# watch.net
KiCad netlist of a schematic drawn in EAGLE
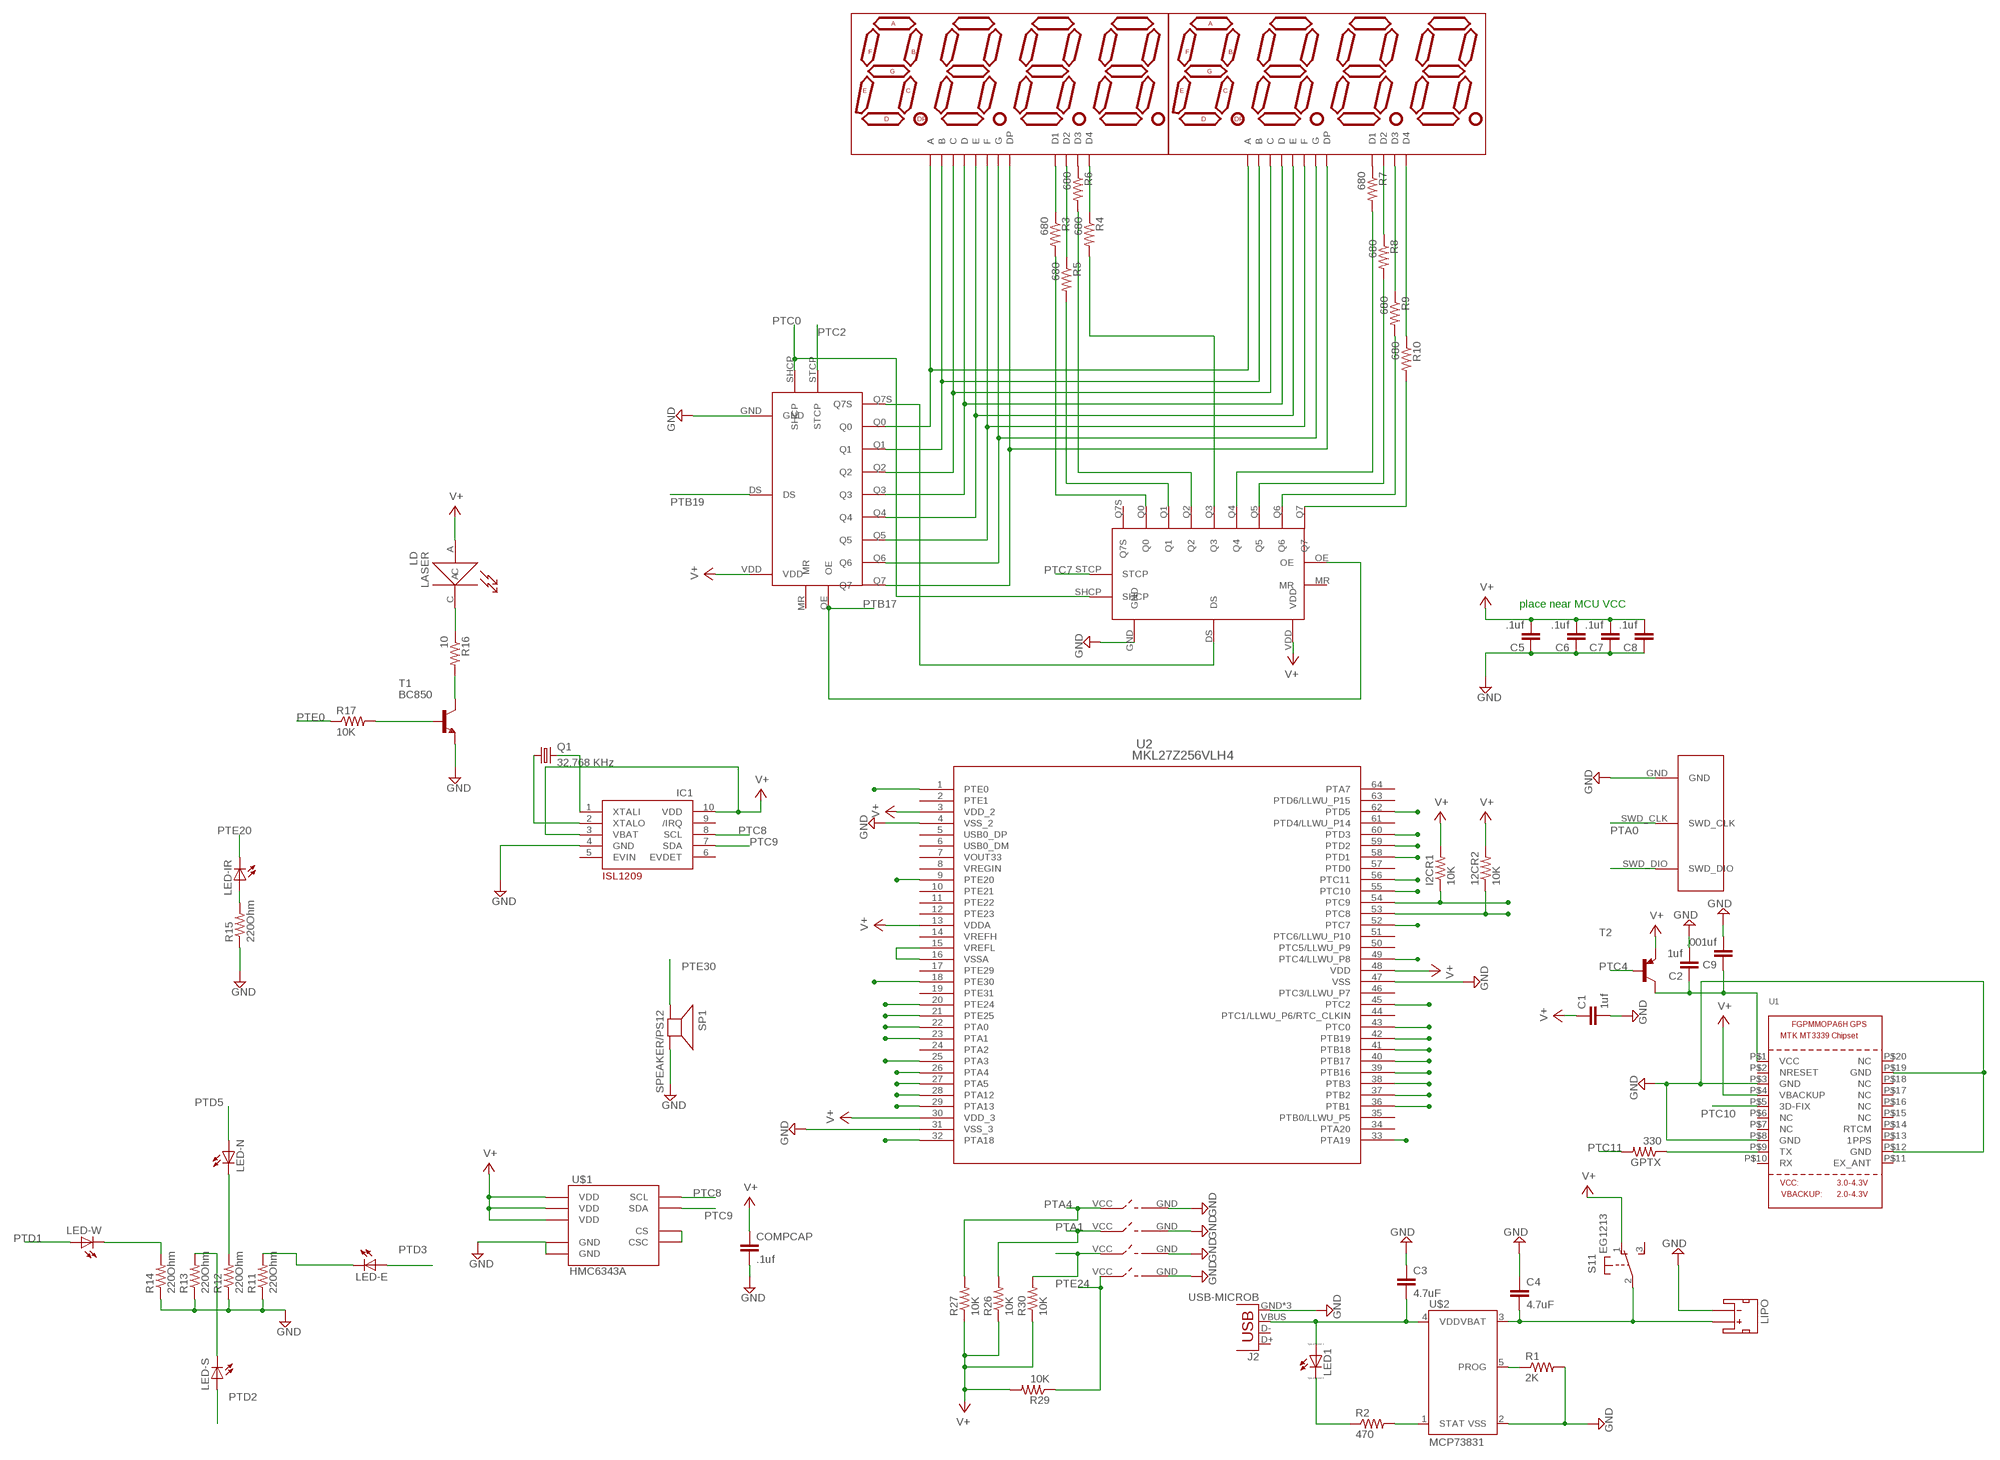
[diagram p0: schematic, sheet 1]

(export (version "E")
  (design (tool "Eeschema 10.0.6"))
  (components
    (comp (ref "12CR2")
      (value "10K")
      (footprint "eagle-import:0603-RES")
      (libsource (lib "eagle-import") (part "RESISTOR0603"))
    )
    (comp (ref "C1")
      (value "1uf")
      (footprint "eagle-import:0603")
      (libsource (lib "eagle-import") (part "CAP0603"))
    )
    (comp (ref "C2")
      (value "1uf")
      (footprint "eagle-import:0603")
      (libsource (lib "eagle-import") (part "CAP0603"))
    )
    (comp (ref "C3")
      (value "4.7uF")
      (footprint "eagle-import:0603-CAP")
      (libsource (lib "eagle-import") (part "0.1UF-25V(+80/-20%)(0603)"))
    )
    (comp (ref "C4")
      (value "4.7uF")
      (footprint "eagle-import:0603-CAP")
      (libsource (lib "eagle-import") (part "0.1UF-25V(+80/-20%)(0603)"))
    )
    (comp (ref "C5")
      (value ".1uf")
      (footprint "eagle-import:0603")
      (libsource (lib "eagle-import") (part "CAP0603"))
    )
    (comp (ref "C6")
      (value ".1uf")
      (footprint "eagle-import:0603")
      (libsource (lib "eagle-import") (part "CAP0603"))
    )
    (comp (ref "C7")
      (value ".1uf")
      (footprint "eagle-import:0603")
      (libsource (lib "eagle-import") (part "CAP0603"))
    )
    (comp (ref "C8")
      (value ".1uf")
      (footprint "eagle-import:0603")
      (libsource (lib "eagle-import") (part "CAP0603"))
    )
    (comp (ref "C9")
      (value ".001uf")
      (footprint "eagle-import:0603")
      (libsource (lib "eagle-import") (part "CAP0603"))
    )
    (comp (ref "COMPCAP")
      (value ".1uf")
      (footprint "eagle-import:0603")
      (libsource (lib "eagle-import") (part "CAP0603"))
    )
    (comp (ref "DISP1")
      (value "7-SEGMENT-4DIGIT-COUNTER-HP-BUBBLE")
      (footprint "eagle-import:DIL12")
      (libsource (lib "eagle-import") (part "7-SEGMENT-4DIGIT-COUNTER-HP-BUBBLE"))
    )
    (comp (ref "DISP2")
      (value "7-SEGMENT-4DIGIT-COUNTER-HP-BUBBLE")
      (footprint "eagle-import:DIL12")
      (libsource (lib "eagle-import") (part "7-SEGMENT-4DIGIT-COUNTER-HP-BUBBLE"))
    )
    (comp (ref "GPTX")
      (value "330")
      (footprint "eagle-import:0603-RES")
      (libsource (lib "eagle-import") (part "RESISTOR0603"))
    )
    (comp (ref "I2CR1")
      (value "10K")
      (footprint "eagle-import:0603-RES")
      (libsource (lib "eagle-import") (part "RESISTOR0603"))
    )
    (comp (ref "IC1")
      (value "ISL1209")
      (footprint "eagle-import:MSOP10")
      (libsource (lib "eagle-import") (part "ISL1209"))
    )
    (comp (ref "J2")
      (value "USB-MICROB")
      (footprint "eagle-import:USB-MICROB")
      (libsource (lib "eagle-import") (part "USB-MICROB"))
    )
    (comp (ref "LASER")
      (value "LD")
      (footprint "eagle-import:LD-FLUSH-WITH-JUMPER")
      (libsource (lib "eagle-import") (part "LD"))
    )
    (comp (ref "LED-E")
      (value "LED5MM")
      (footprint "eagle-import:LED5MM")
      (libsource (lib "eagle-import") (part "LED5MM"))
    )
    (comp (ref "LED-IR")
      (value "LED5MM")
      (footprint "eagle-import:LED5MM")
      (libsource (lib "eagle-import") (part "LED5MM"))
    )
    (comp (ref "LED-N")
      (value "LED5MM")
      (footprint "eagle-import:LED5MM")
      (libsource (lib "eagle-import") (part "LED5MM"))
    )
    (comp (ref "LED-S")
      (value "LED5MM")
      (footprint "eagle-import:LED5MM")
      (libsource (lib "eagle-import") (part "LED5MM"))
    )
    (comp (ref "LED-W")
      (value "LED5MM")
      (footprint "eagle-import:LED5MM")
      (libsource (lib "eagle-import") (part "LED5MM"))
    )
    (comp (ref "LED1")
      (value "LED_ESML0603")
      (footprint "eagle-import:LED_SML0603")
      (libsource (lib "eagle-import") (part "LED_ESML0603"))
    )
    (comp (ref "LIPO")
      (value "JST_2MM_MALE")
      (footprint "eagle-import:JST-2-SMD")
      (libsource (lib "eagle-import") (part "JST_2MM_MALE"))
    )
    (comp (ref "Q1")
      (value "32.768 KHz")
      (footprint "eagle-import:TC26H")
      (libsource (lib "eagle-import") (part "CRYSTALTC26H"))
    )
    (comp (ref "R1")
      (value "2K")
      (footprint "eagle-import:0603-RES")
      (libsource (lib "eagle-import") (part "RESISTOR0603"))
    )
    (comp (ref "R2")
      (value "470")
      (footprint "eagle-import:0603-RES")
      (libsource (lib "eagle-import") (part "RESISTOR0603"))
    )
    (comp (ref "R3")
      (value "680")
      (footprint "eagle-import:0603-RES")
      (libsource (lib "eagle-import") (part "RESISTOR0603"))
    )
    (comp (ref "R4")
      (value "680")
      (footprint "eagle-import:0603-RES")
      (libsource (lib "eagle-import") (part "RESISTOR0603"))
    )
    (comp (ref "R5")
      (value "680")
      (footprint "eagle-import:0603-RES")
      (libsource (lib "eagle-import") (part "RESISTOR0603"))
    )
    (comp (ref "R6")
      (value "680")
      (footprint "eagle-import:0603-RES")
      (libsource (lib "eagle-import") (part "RESISTOR0603"))
    )
    (comp (ref "R7")
      (value "680")
      (footprint "eagle-import:0603-RES")
      (libsource (lib "eagle-import") (part "RESISTOR0603"))
    )
    (comp (ref "R8")
      (value "680")
      (footprint "eagle-import:0603-RES")
      (libsource (lib "eagle-import") (part "RESISTOR0603"))
    )
    (comp (ref "R9")
      (value "680")
      (footprint "eagle-import:0603-RES")
      (libsource (lib "eagle-import") (part "RESISTOR0603"))
    )
    (comp (ref "R10")
      (value "680")
      (footprint "eagle-import:0603-RES")
      (libsource (lib "eagle-import") (part "RESISTOR0603"))
    )
    (comp (ref "R11")
      (value "220Ohm")
      (footprint "eagle-import:0603-RES")
      (libsource (lib "eagle-import") (part "RESISTOR0603"))
    )
    (comp (ref "R12")
      (value "220Ohm")
      (footprint "eagle-import:0603-RES")
      (libsource (lib "eagle-import") (part "RESISTOR0603"))
    )
    (comp (ref "R13")
      (value "220Ohm")
      (footprint "eagle-import:0603-RES")
      (libsource (lib "eagle-import") (part "RESISTOR0603"))
    )
    (comp (ref "R14")
      (value "220Ohm")
      (footprint "eagle-import:0603-RES")
      (libsource (lib "eagle-import") (part "RESISTOR0603"))
    )
    (comp (ref "R15")
      (value "220Ohm")
      (footprint "eagle-import:0603-RES")
      (libsource (lib "eagle-import") (part "RESISTOR0603"))
    )
    (comp (ref "R16")
      (value "10")
      (footprint "eagle-import:0603-RES")
      (libsource (lib "eagle-import") (part "RESISTOR0603"))
    )
    (comp (ref "R17")
      (value "10K")
      (footprint "eagle-import:0603-RES")
      (libsource (lib "eagle-import") (part "RESISTOR0603"))
    )
    (comp (ref "R26")
      (value "10K")
      (footprint "eagle-import:0603-RES")
      (libsource (lib "eagle-import") (part "RESISTOR0603"))
    )
    (comp (ref "R27")
      (value "10K")
      (footprint "eagle-import:0603-RES")
      (libsource (lib "eagle-import") (part "RESISTOR0603"))
    )
    (comp (ref "R29")
      (value "10K")
      (footprint "eagle-import:0603-RES")
      (libsource (lib "eagle-import") (part "RESISTOR0603"))
    )
    (comp (ref "R30")
      (value "10K")
      (footprint "eagle-import:0603-RES")
      (libsource (lib "eagle-import") (part "RESISTOR0603"))
    )
    (comp (ref "S1")
      (value "EG1213")
      (footprint "eagle-import:EG1213")
      (libsource (lib "eagle-import") (part "EG1213"))
    )
    (comp (ref "SP1")
      (value "SPEAKER/PS12")
      (footprint "eagle-import:PS12")
      (libsource (lib "eagle-import") (part "SPEAKER/PS12"))
    )
    (comp (ref "SWD_BREAKOUT")
      (value "SWD_BREAKOUTS")
      (footprint "eagle-import:SWD")
      (libsource (lib "eagle-import") (part "SWD_BREAKOUTS"))
    )
    (comp (ref "T1")
      (value "BC850")
      (footprint "eagle-import:SOT23")
      (libsource (lib "eagle-import") (part "BC850"))
    )
    (comp (ref "T2")
      (value "-PNP-SOT23-EBC")
      (footprint "eagle-import:SOT23-EBC")
      (libsource (lib "eagle-import") (part "-PNP-SOT23-EBC"))
    )
    (comp (ref "U$1")
      (value "HMC6343A")
      (footprint "eagle-import:LCC36")
      (libsource (lib "eagle-import") (part "HMC6343A"))
    )
    (comp (ref "U$2")
      (value "MCP73831")
      (footprint "eagle-import:SOT23-5")
      (libsource (lib "eagle-import") (part "MCP73831"))
    )
    (comp (ref "U$3")
      (value "DIPS")
      (footprint "eagle-import:DIPS")
      (libsource (lib "eagle-import") (part "DIPS"))
    )
    (comp (ref "U$4")
      (value "74HC595PW")
      (footprint "eagle-import:74HC595PW")
      (libsource (lib "eagle-import") (part "74HC595PW"))
    )
    (comp (ref "U$5")
      (value "74HC595PW")
      (footprint "eagle-import:74HC595PW")
      (libsource (lib "eagle-import") (part "74HC595PW"))
    )
    (comp (ref "U$7")
      (value "DIPS")
      (footprint "eagle-import:DIPS")
      (libsource (lib "eagle-import") (part "DIPS"))
    )
    (comp (ref "U$8")
      (value "DIPS")
      (footprint "eagle-import:DIPS")
      (libsource (lib "eagle-import") (part "DIPS"))
    )
    (comp (ref "U$9")
      (value "DIPS")
      (footprint "eagle-import:DIPS")
      (libsource (lib "eagle-import") (part "DIPS"))
    )
    (comp (ref "U1")
      (value "GPS_FGPMMOPA6H")
      (footprint "eagle-import:FGPMMOPA6H")
      (libsource (lib "eagle-import") (part "GPS_FGPMMOPA6H"))
    )
    (comp (ref "U2")
      (value "MKL27Z256VLH4")
      (footprint "eagle-import:LQFP-64_10X10X1.6")
      (fields (field (name "MANUFACTURER_PART_NUMBER") "mkl27z256vlh4"))
      (libsource (lib "eagle-import") (part "MKL27Z256VLH4"))
    )
  )
  (nets
    (net (code "1") (name "/PTA0") (class "Default")
      (node (ref "SWD_BREAKOUT") (pin "SWD_CLK") (pinfunction "SWD_CLK_SWD_CLK") (pintype "bidirectional"))
      (node (ref "U2") (pin "22") (pinfunction "PTA0_22") (pintype "bidirectional"))
    )
    (net (code "2") (name "/PTA1") (class "Default")
      (node (ref "R26") (pin "2") (pinfunction "2_2") (pintype "passive"))
      (node (ref "U$7") (pin "VCC") (pinfunction "V_VCC") (pintype "bidirectional"))
      (node (ref "U2") (pin "23") (pinfunction "PTA1_23") (pintype "bidirectional"))
    )
    (net (code "3") (name "/PTA3") (class "Default")
      (node (ref "SWD_BREAKOUT") (pin "SWD_DIO") (pinfunction "SWD_DIO_SWD_DIO") (pintype "bidirectional"))
      (node (ref "U2") (pin "25") (pinfunction "PTA3_25") (pintype "bidirectional"))
    )
    (net (code "4") (name "/PTA4") (class "Default")
      (node (ref "R27") (pin "2") (pinfunction "2_2") (pintype "passive"))
      (node (ref "U$3") (pin "VCC") (pinfunction "V_VCC") (pintype "bidirectional"))
      (node (ref "U2") (pin "26") (pinfunction "PTA4_26") (pintype "bidirectional"))
    )
    (net (code "5") (name "/PTB17") (class "Default")
      (node (ref "U$4") (pin "OE") (pinfunction "OE_OE") (pintype "bidirectional"))
      (node (ref "U$5") (pin "OE") (pinfunction "OE_OE") (pintype "bidirectional"))
      (node (ref "U2") (pin "40") (pinfunction "PTB17_40") (pintype "bidirectional"))
    )
    (net (code "6") (name "/PTB19") (class "Default")
      (node (ref "U$4") (pin "DS") (pinfunction "DS_DS") (pintype "bidirectional"))
      (node (ref "U2") (pin "42") (pinfunction "PTB19_42") (pintype "bidirectional"))
    )
    (net (code "7") (name "/PTC0") (class "Default")
      (node (ref "U$4") (pin "SHCP") (pinfunction "SHCP_SHCP") (pintype "bidirectional"))
      (node (ref "U$5") (pin "SHCP") (pinfunction "SHCP_SHCP") (pintype "bidirectional"))
      (node (ref "U2") (pin "43") (pinfunction "PTC0_43") (pintype "bidirectional"))
    )
    (net (code "8") (name "/PTC2") (class "Default")
      (node (ref "U$4") (pin "STCP") (pinfunction "STCP_STCP") (pintype "bidirectional"))
      (node (ref "U2") (pin "45") (pinfunction "PTC2_45") (pintype "bidirectional"))
    )
    (net (code "9") (name "/PTC4") (class "Default")
      (node (ref "T2") (pin "B") (pinfunction "B_B") (pintype "passive"))
      (node (ref "U2") (pin "49") (pinfunction "PTC4/LLWU_P8_49") (pintype "bidirectional"))
    )
    (net (code "10") (name "/PTC7") (class "Default")
      (node (ref "U$5") (pin "STCP") (pinfunction "STCP_STCP") (pintype "bidirectional"))
      (node (ref "U2") (pin "52") (pinfunction "PTC7_52") (pintype "bidirectional"))
    )
    (net (code "11") (name "/PTC8") (class "Default")
      (node (ref "12CR2") (pin "1") (pinfunction "1_1") (pintype "passive"))
      (node (ref "IC1") (pin "8") (pinfunction "SCL_8") (pintype "input"))
      (node (ref "U$1") (pin "32") (pinfunction "SCL_32") (pintype "bidirectional"))
      (node (ref "U2") (pin "53") (pinfunction "PTC8_53") (pintype "bidirectional"))
    )
    (net (code "12") (name "/PTC9") (class "Default")
      (node (ref "I2CR1") (pin "1") (pinfunction "1_1") (pintype "passive"))
      (node (ref "IC1") (pin "7") (pinfunction "SDA_7") (pintype "bidirectional"))
      (node (ref "U$1") (pin "36") (pinfunction "SDA_36") (pintype "bidirectional"))
      (node (ref "U2") (pin "54") (pinfunction "PTC9_54") (pintype "bidirectional"))
    )
    (net (code "13") (name "/PTC10") (class "Default")
      (node (ref "U1") (pin "P$5") (pinfunction "3D-FIX_P$5") (pintype "bidirectional"))
      (node (ref "U2") (pin "55") (pinfunction "PTC10_55") (pintype "bidirectional"))
    )
    (net (code "14") (name "/PTC11") (class "Default")
      (node (ref "GPTX") (pin "2") (pinfunction "2_2") (pintype "passive"))
      (node (ref "U2") (pin "56") (pinfunction "PTC11_56") (pintype "bidirectional"))
    )
    (net (code "15") (name "/PTD1") (class "Default")
      (node (ref "LED-W") (pin "A") (pinfunction "A_A") (pintype "passive"))
      (node (ref "U2") (pin "58") (pinfunction "PTD1_58") (pintype "bidirectional"))
    )
    (net (code "16") (name "/PTD2") (class "Default")
      (node (ref "LED-S") (pin "A") (pinfunction "A_A") (pintype "passive"))
      (node (ref "U2") (pin "59") (pinfunction "PTD2_59") (pintype "bidirectional"))
    )
    (net (code "17") (name "/PTD3") (class "Default")
      (node (ref "LED-E") (pin "A") (pinfunction "A_A") (pintype "passive"))
      (node (ref "U2") (pin "60") (pinfunction "PTD3_60") (pintype "bidirectional"))
    )
    (net (code "18") (name "/PTD5") (class "Default")
      (node (ref "LED-N") (pin "A") (pinfunction "A_A") (pintype "passive"))
      (node (ref "U2") (pin "62") (pinfunction "PTD5_62") (pintype "bidirectional"))
    )
    (net (code "19") (name "/PTE0") (class "Default")
      (node (ref "R17") (pin "1") (pinfunction "1_1") (pintype "passive"))
      (node (ref "U2") (pin "1") (pinfunction "PTE0_1") (pintype "bidirectional"))
    )
    (net (code "20") (name "/PTE20") (class "Default")
      (node (ref "LED-IR") (pin "K") (pinfunction "C_K") (pintype "passive"))
      (node (ref "U2") (pin "9") (pinfunction "PTE20_9") (pintype "bidirectional"))
    )
    (net (code "21") (name "/PTE24") (class "Default")
      (node (ref "R29") (pin "1") (pinfunction "1_1") (pintype "passive"))
      (node (ref "U$9") (pin "VCC") (pinfunction "V_VCC") (pintype "bidirectional"))
      (node (ref "U2") (pin "20") (pinfunction "PTE24_20") (pintype "bidirectional"))
    )
    (net (code "22") (name "/PTE25") (class "Default")
      (node (ref "R30") (pin "2") (pinfunction "2_2") (pintype "passive"))
      (node (ref "U$8") (pin "VCC") (pinfunction "V_VCC") (pintype "bidirectional"))
      (node (ref "U2") (pin "21") (pinfunction "PTE25_21") (pintype "bidirectional"))
    )
    (net (code "23") (name "/PTE30") (class "Default")
      (node (ref "SP1") (pin "P$1") (pinfunction "+_P$1") (pintype "passive"))
      (node (ref "U2") (pin "18") (pinfunction "PTE30_18") (pintype "bidirectional"))
    )
    (net (code "24") (name "/VREFH") (class "Default")
      (node (ref "U2") (pin "14") (pinfunction "VREFH_14") (pintype "power_in"))
    )
    (net (code "25") (name "GND") (class "Default")
      (node (ref "C1") (pin "2") (pinfunction "2_2") (pintype "passive"))
      (node (ref "C2") (pin "2") (pinfunction "2_2") (pintype "passive"))
      (node (ref "C3") (pin "1") (pinfunction "1_1") (pintype "passive"))
      (node (ref "C4") (pin "1") (pinfunction "1_1") (pintype "passive"))
      (node (ref "C5") (pin "1") (pinfunction "1_1") (pintype "passive"))
      (node (ref "C6") (pin "1") (pinfunction "1_1") (pintype "passive"))
      (node (ref "C7") (pin "1") (pinfunction "1_1") (pintype "passive"))
      (node (ref "C8") (pin "1") (pinfunction "1_1") (pintype "passive"))
      (node (ref "C9") (pin "2") (pinfunction "2_2") (pintype "passive"))
      (node (ref "COMPCAP") (pin "2") (pinfunction "2_2") (pintype "passive"))
      (node (ref "IC1") (pin "4") (pinfunction "GND_4") (pintype "power_in"))
      (node (ref "J2") (pin "GND") (pinfunction "GND_GND") (pintype "bidirectional"))
      (node (ref "J2") (pin "MT1") (pinfunction "GND_MT1") (pintype "bidirectional"))
      (node (ref "J2") (pin "MT2") (pinfunction "GND_MT2") (pintype "bidirectional"))
      (node (ref "LIPO") (pin "1") (pinfunction "-_1") (pintype "bidirectional"))
      (node (ref "R1") (pin "2") (pinfunction "2_2") (pintype "passive"))
      (node (ref "R11") (pin "1") (pinfunction "1_1") (pintype "passive"))
      (node (ref "R12") (pin "1") (pinfunction "1_1") (pintype "passive"))
      (node (ref "R13") (pin "1") (pinfunction "1_1") (pintype "passive"))
      (node (ref "R14") (pin "1") (pinfunction "1_1") (pintype "passive"))
      (node (ref "R15") (pin "1") (pinfunction "1_1") (pintype "passive"))
      (node (ref "SP1") (pin "P$2") (pinfunction "-_P$2") (pintype "passive"))
      (node (ref "SWD_BREAKOUT") (pin "GND") (pinfunction "GND_GND") (pintype "bidirectional"))
      (node (ref "T1") (pin "2") (pinfunction "E_2") (pintype "passive"))
      (node (ref "U$1") (pin "25") (pinfunction "GND_25") (pintype "bidirectional"))
      (node (ref "U$1") (pin "29") (pinfunction "GND_29") (pintype "bidirectional"))
      (node (ref "U$2") (pin "2") (pinfunction "VSS_2") (pintype "power_in"))
      (node (ref "U$3") (pin "GND") (pinfunction "GND_GND") (pintype "bidirectional"))
      (node (ref "U$4") (pin "GND") (pinfunction "GND_GND") (pintype "bidirectional"))
      (node (ref "U$5") (pin "GND") (pinfunction "GND_GND") (pintype "bidirectional"))
      (node (ref "U$7") (pin "GND") (pinfunction "GND_GND") (pintype "bidirectional"))
      (node (ref "U$8") (pin "GND") (pinfunction "GND_GND") (pintype "bidirectional"))
      (node (ref "U$9") (pin "GND") (pinfunction "GND_GND") (pintype "bidirectional"))
      (node (ref "U1") (pin "P$12") (pinfunction "GND_P$12") (pintype "bidirectional"))
      (node (ref "U1") (pin "P$19") (pinfunction "GND_P$19") (pintype "bidirectional"))
      (node (ref "U1") (pin "P$3") (pinfunction "GND_P$3") (pintype "bidirectional"))
      (node (ref "U1") (pin "P$8") (pinfunction "GND_P$8") (pintype "bidirectional"))
      (node (ref "U2") (pin "31") (pinfunction "VSS_3_31") (pintype "power_in"))
      (node (ref "U2") (pin "4") (pinfunction "VSS_2_4") (pintype "power_in"))
      (node (ref "U2") (pin "47") (pinfunction "VSS_47") (pintype "power_in"))
    )
    (net (code "26") (name "Net-(DISP1-A)") (class "Default")
      (node (ref "DISP1") (pin "12") (pinfunction "A_12") (pintype "bidirectional"))
      (node (ref "DISP2") (pin "12") (pinfunction "A_12") (pintype "bidirectional"))
      (node (ref "U$4") (pin "Q0") (pinfunction "Q0_Q0") (pintype "bidirectional"))
    )
    (net (code "27") (name "Net-(DISP1-B)") (class "Default")
      (node (ref "DISP1") (pin "11") (pinfunction "B_11") (pintype "bidirectional"))
      (node (ref "DISP2") (pin "11") (pinfunction "B_11") (pintype "bidirectional"))
      (node (ref "U$4") (pin "Q1") (pinfunction "Q1_Q1") (pintype "bidirectional"))
    )
    (net (code "28") (name "Net-(DISP1-C)") (class "Default")
      (node (ref "DISP1") (pin "3") (pinfunction "C_3") (pintype "bidirectional"))
      (node (ref "DISP2") (pin "3") (pinfunction "C_3") (pintype "bidirectional"))
      (node (ref "U$4") (pin "Q2") (pinfunction "Q2_Q2") (pintype "bidirectional"))
    )
    (net (code "29") (name "Net-(DISP1-D)") (class "Default")
      (node (ref "DISP1") (pin "8") (pinfunction "D_8") (pintype "bidirectional"))
      (node (ref "DISP2") (pin "8") (pinfunction "D_8") (pintype "bidirectional"))
      (node (ref "U$4") (pin "Q3") (pinfunction "Q3_Q3") (pintype "bidirectional"))
    )
    (net (code "30") (name "Net-(DISP1-D1)") (class "Default")
      (node (ref "DISP1") (pin "1") (pinfunction "D1_1") (pintype "bidirectional"))
      (node (ref "R3") (pin "1") (pinfunction "1_1") (pintype "passive"))
    )
    (net (code "31") (name "Net-(DISP1-D2)") (class "Default")
      (node (ref "DISP1") (pin "10") (pinfunction "D2_10") (pintype "bidirectional"))
      (node (ref "R5") (pin "1") (pinfunction "1_1") (pintype "passive"))
    )
    (net (code "32") (name "Net-(DISP1-D3)") (class "Default")
      (node (ref "DISP1") (pin "4") (pinfunction "D3_4") (pintype "bidirectional"))
      (node (ref "R6") (pin "1") (pinfunction "1_1") (pintype "passive"))
    )
    (net (code "33") (name "Net-(DISP1-D4)") (class "Default")
      (node (ref "DISP1") (pin "6") (pinfunction "D4_6") (pintype "bidirectional"))
      (node (ref "R4") (pin "1") (pinfunction "1_1") (pintype "passive"))
    )
    (net (code "34") (name "Net-(DISP1-DP)") (class "Default")
      (node (ref "DISP1") (pin "5") (pinfunction "DP_5") (pintype "bidirectional"))
      (node (ref "DISP2") (pin "5") (pinfunction "DP_5") (pintype "bidirectional"))
      (node (ref "U$4") (pin "Q7") (pinfunction "Q7_Q7") (pintype "bidirectional"))
    )
    (net (code "35") (name "Net-(DISP1-E)") (class "Default")
      (node (ref "DISP1") (pin "2") (pinfunction "E_2") (pintype "bidirectional"))
      (node (ref "DISP2") (pin "2") (pinfunction "E_2") (pintype "bidirectional"))
      (node (ref "U$4") (pin "Q4") (pinfunction "Q4_Q4") (pintype "bidirectional"))
    )
    (net (code "36") (name "Net-(DISP1-F)") (class "Default")
      (node (ref "DISP1") (pin "9") (pinfunction "F_9") (pintype "bidirectional"))
      (node (ref "DISP2") (pin "9") (pinfunction "F_9") (pintype "bidirectional"))
      (node (ref "U$4") (pin "Q5") (pinfunction "Q5_Q5") (pintype "bidirectional"))
    )
    (net (code "37") (name "Net-(DISP1-G)") (class "Default")
      (node (ref "DISP1") (pin "7") (pinfunction "G_7") (pintype "bidirectional"))
      (node (ref "DISP2") (pin "7") (pinfunction "G_7") (pintype "bidirectional"))
      (node (ref "U$4") (pin "Q6") (pinfunction "Q6_Q6") (pintype "bidirectional"))
    )
    (net (code "38") (name "Net-(DISP2-D1)") (class "Default")
      (node (ref "DISP2") (pin "1") (pinfunction "D1_1") (pintype "bidirectional"))
      (node (ref "R7") (pin "1") (pinfunction "1_1") (pintype "passive"))
    )
    (net (code "39") (name "Net-(DISP2-D2)") (class "Default")
      (node (ref "DISP2") (pin "10") (pinfunction "D2_10") (pintype "bidirectional"))
      (node (ref "R8") (pin "1") (pinfunction "1_1") (pintype "passive"))
    )
    (net (code "40") (name "Net-(DISP2-D3)") (class "Default")
      (node (ref "DISP2") (pin "4") (pinfunction "D3_4") (pintype "bidirectional"))
      (node (ref "R9") (pin "1") (pinfunction "1_1") (pintype "passive"))
    )
    (net (code "41") (name "Net-(DISP2-D4)") (class "Default")
      (node (ref "DISP2") (pin "6") (pinfunction "D4_6") (pintype "bidirectional"))
      (node (ref "R10") (pin "1") (pinfunction "1_1") (pintype "passive"))
    )
    (net (code "42") (name "Net-(IC1-XTALI)") (class "Default")
      (node (ref "IC1") (pin "1") (pinfunction "XTALI_1") (pintype "input"))
      (node (ref "Q1") (pin "2") (pinfunction "2_2") (pintype "passive"))
    )
    (net (code "43") (name "Net-(IC1-XTALO)") (class "Default")
      (node (ref "IC1") (pin "2") (pinfunction "XTALO_2") (pintype "output"))
      (node (ref "Q1") (pin "1") (pinfunction "1_1") (pintype "passive"))
    )
    (net (code "44") (name "Net-(LASER-PadC)") (class "Default")
      (node (ref "LASER") (pin "C") (pinfunction "C_C") (pintype "passive"))
      (node (ref "R16") (pin "1") (pinfunction "1_1") (pintype "passive"))
    )
    (net (code "45") (name "Net-(LED-E-C)") (class "Default")
      (node (ref "LED-E") (pin "K") (pinfunction "C_K") (pintype "passive"))
      (node (ref "R11") (pin "2") (pinfunction "2_2") (pintype "passive"))
    )
    (net (code "46") (name "Net-(LED-IR-PadA)") (class "Default")
      (node (ref "LED-IR") (pin "A") (pinfunction "A_A") (pintype "passive"))
      (node (ref "R15") (pin "2") (pinfunction "2_2") (pintype "passive"))
    )
    (net (code "47") (name "Net-(LED-N-C)") (class "Default")
      (node (ref "LED-N") (pin "K") (pinfunction "C_K") (pintype "passive"))
      (node (ref "R12") (pin "2") (pinfunction "2_2") (pintype "passive"))
    )
    (net (code "48") (name "Net-(LED-S-C)") (class "Default")
      (node (ref "LED-S") (pin "K") (pinfunction "C_K") (pintype "passive"))
      (node (ref "R13") (pin "2") (pinfunction "2_2") (pintype "passive"))
    )
    (net (code "49") (name "Net-(LED-W-C)") (class "Default")
      (node (ref "LED-W") (pin "K") (pinfunction "C_K") (pintype "passive"))
      (node (ref "R14") (pin "2") (pinfunction "2_2") (pintype "passive"))
    )
    (net (code "50") (name "Net-(LED1-PadC)") (class "Default")
      (node (ref "LED1") (pin "C") (pinfunction "C_C") (pintype "passive"))
      (node (ref "R2") (pin "1") (pinfunction "1_1") (pintype "passive"))
    )
    (net (code "51") (name "Net-(LIPO-+)") (class "Default")
      (node (ref "C4") (pin "2") (pinfunction "2_2") (pintype "passive"))
      (node (ref "LIPO") (pin "2") (pinfunction "+_2") (pintype "bidirectional"))
      (node (ref "S1") (pin "2") (pinfunction "P_2") (pintype "passive"))
      (node (ref "U$2") (pin "3") (pinfunction "VBAT_3") (pintype "power_in"))
    )
    (net (code "52") (name "Net-(R3-Pad2)") (class "Default")
      (node (ref "R3") (pin "2") (pinfunction "2_2") (pintype "passive"))
      (node (ref "U$5") (pin "Q0") (pinfunction "Q0_Q0") (pintype "bidirectional"))
    )
    (net (code "53") (name "Net-(R4-Pad2)") (class "Default")
      (node (ref "R4") (pin "2") (pinfunction "2_2") (pintype "passive"))
      (node (ref "U$5") (pin "Q3") (pinfunction "Q3_Q3") (pintype "bidirectional"))
    )
    (net (code "54") (name "Net-(R5-Pad2)") (class "Default")
      (node (ref "R5") (pin "2") (pinfunction "2_2") (pintype "passive"))
      (node (ref "U$5") (pin "Q1") (pinfunction "Q1_Q1") (pintype "bidirectional"))
    )
    (net (code "55") (name "Net-(R6-Pad2)") (class "Default")
      (node (ref "R6") (pin "2") (pinfunction "2_2") (pintype "passive"))
      (node (ref "U$5") (pin "Q2") (pinfunction "Q2_Q2") (pintype "bidirectional"))
    )
    (net (code "56") (name "Net-(R7-Pad2)") (class "Default")
      (node (ref "R7") (pin "2") (pinfunction "2_2") (pintype "passive"))
      (node (ref "U$5") (pin "Q4") (pinfunction "Q4_Q4") (pintype "bidirectional"))
    )
    (net (code "57") (name "Net-(R8-Pad2)") (class "Default")
      (node (ref "R8") (pin "2") (pinfunction "2_2") (pintype "passive"))
      (node (ref "U$5") (pin "Q5") (pinfunction "Q5_Q5") (pintype "bidirectional"))
    )
    (net (code "58") (name "Net-(R9-Pad2)") (class "Default")
      (node (ref "R9") (pin "2") (pinfunction "2_2") (pintype "passive"))
      (node (ref "U$5") (pin "Q6") (pinfunction "Q6_Q6") (pintype "bidirectional"))
    )
    (net (code "59") (name "Net-(R10-Pad2)") (class "Default")
      (node (ref "R10") (pin "2") (pinfunction "2_2") (pintype "passive"))
      (node (ref "U$5") (pin "Q7") (pinfunction "Q7_Q7") (pintype "bidirectional"))
    )
    (net (code "60") (name "Net-(T1-B)") (class "Default")
      (node (ref "R17") (pin "2") (pinfunction "2_2") (pintype "passive"))
      (node (ref "T1") (pin "1") (pinfunction "B_1") (pintype "passive"))
    )
    (net (code "61") (name "Net-(T1-C)") (class "Default")
      (node (ref "R16") (pin "2") (pinfunction "2_2") (pintype "passive"))
      (node (ref "T1") (pin "3") (pinfunction "C_3") (pintype "passive"))
    )
    (net (code "62") (name "Net-(U$1-CS)") (class "Default")
      (node (ref "U$1") (pin "22") (pinfunction "CS_22") (pintype "bidirectional"))
      (node (ref "U$1") (pin "35") (pinfunction "CSC_35") (pintype "bidirectional"))
    )
    (net (code "63") (name "Net-(U$2-PROG)") (class "Default")
      (node (ref "R1") (pin "1") (pinfunction "1_1") (pintype "passive"))
      (node (ref "U$2") (pin "5") (pinfunction "PROG_5") (pintype "input"))
    )
    (net (code "64") (name "Net-(U$2-STAT)") (class "Default")
      (node (ref "R2") (pin "2") (pinfunction "2_2") (pintype "passive"))
      (node (ref "U$2") (pin "1") (pinfunction "STAT_1") (pintype "output"))
    )
    (net (code "65") (name "Net-(U$2-VDD)") (class "Default")
      (node (ref "C3") (pin "2") (pinfunction "2_2") (pintype "passive"))
      (node (ref "J2") (pin "VBUS") (pinfunction "VBUS_VBUS") (pintype "bidirectional"))
      (node (ref "LED1") (pin "A") (pinfunction "A_A") (pintype "passive"))
      (node (ref "U$2") (pin "4") (pinfunction "VDD_4") (pintype "power_in"))
    )
    (net (code "66") (name "Net-(U$4-PadQ7S)") (class "Default")
      (node (ref "U$4") (pin "Q7S") (pinfunction "Q7S_Q7S") (pintype "bidirectional"))
      (node (ref "U$5") (pin "DS") (pinfunction "DS_DS") (pintype "bidirectional"))
    )
    (net (code "67") (name "Net-(U1-TX)") (class "Default")
      (node (ref "GPTX") (pin "1") (pinfunction "1_1") (pintype "passive"))
      (node (ref "U1") (pin "P$9") (pinfunction "TX_P$9") (pintype "bidirectional"))
    )
    (net (code "68") (name "Net-(U1-VCC)") (class "Default")
      (node (ref "C2") (pin "1") (pinfunction "1_1") (pintype "passive"))
      (node (ref "C9") (pin "1") (pinfunction "1_1") (pintype "passive"))
      (node (ref "T2") (pin "C") (pinfunction "C_C") (pintype "passive"))
      (node (ref "U1") (pin "P$1") (pinfunction "VCC_P$1") (pintype "bidirectional"))
    )
    (net (code "69") (name "Net-(U2-VREFL)") (class "Default")
      (node (ref "U2") (pin "15") (pinfunction "VREFL_15") (pintype "power_in"))
      (node (ref "U2") (pin "16") (pinfunction "VSSA_16") (pintype "power_in"))
    )
    (net (code "70") (name "V+") (class "Default")
      (node (ref "12CR2") (pin "2") (pinfunction "2_2") (pintype "passive"))
      (node (ref "C1") (pin "1") (pinfunction "1_1") (pintype "passive"))
      (node (ref "C5") (pin "2") (pinfunction "2_2") (pintype "passive"))
      (node (ref "C6") (pin "2") (pinfunction "2_2") (pintype "passive"))
      (node (ref "C7") (pin "2") (pinfunction "2_2") (pintype "passive"))
      (node (ref "C8") (pin "2") (pinfunction "2_2") (pintype "passive"))
      (node (ref "COMPCAP") (pin "1") (pinfunction "1_1") (pintype "passive"))
      (node (ref "I2CR1") (pin "2") (pinfunction "2_2") (pintype "passive"))
      (node (ref "IC1") (pin "10") (pinfunction "VDD_10") (pintype "power_in"))
      (node (ref "IC1") (pin "3") (pinfunction "VBAT_3") (pintype "power_in"))
      (node (ref "LASER") (pin "A") (pinfunction "A_A") (pintype "passive"))
      (node (ref "R26") (pin "1") (pinfunction "1_1") (pintype "passive"))
      (node (ref "R27") (pin "1") (pinfunction "1_1") (pintype "passive"))
      (node (ref "R29") (pin "2") (pinfunction "2_2") (pintype "passive"))
      (node (ref "R30") (pin "1") (pinfunction "1_1") (pintype "passive"))
      (node (ref "S1") (pin "1") (pinfunction "O_1") (pintype "passive"))
      (node (ref "T2") (pin "E") (pinfunction "E_E") (pintype "passive"))
      (node (ref "U$1") (pin "11") (pinfunction "VDD_11") (pintype "bidirectional"))
      (node (ref "U$1") (pin "21") (pinfunction "VDD_21") (pintype "bidirectional"))
      (node (ref "U$1") (pin "3") (pinfunction "VDD_3") (pintype "bidirectional"))
      (node (ref "U$4") (pin "VDD") (pinfunction "VDD_VDD") (pintype "bidirectional"))
      (node (ref "U$5") (pin "VDD") (pinfunction "VDD_VDD") (pintype "bidirectional"))
      (node (ref "U1") (pin "P$4") (pinfunction "VBACKUP_P$4") (pintype "bidirectional"))
      (node (ref "U2") (pin "13") (pinfunction "VDDA_13") (pintype "power_in"))
      (node (ref "U2") (pin "3") (pinfunction "VDD_2_3") (pintype "power_in"))
      (node (ref "U2") (pin "30") (pinfunction "VDD_3_30") (pintype "power_in"))
      (node (ref "U2") (pin "48") (pinfunction "VDD_48") (pintype "power_in"))
    )
    (net (code "71") (name "unconnected-(IC1-EVDET-Pad6)") (class "Default")
      (node (ref "IC1") (pin "6") (pinfunction "EVDET_6") (pintype "output"))
    )
    (net (code "72") (name "unconnected-(IC1-EVIN-Pad5)") (class "Default")
      (node (ref "IC1") (pin "5") (pinfunction "EVIN_5") (pintype "input"))
    )
    (net (code "73") (name "unconnected-(IC1-{slash}IRQ-Pad9)") (class "Default")
      (node (ref "IC1") (pin "9") (pinfunction "/IRQ_9") (pintype "output"))
    )
    (net (code "74") (name "unconnected-(J2-PadD+)") (class "Default")
      (node (ref "J2") (pin "D+") (pinfunction "D+_D+") (pintype "bidirectional"))
    )
    (net (code "75") (name "unconnected-(J2-PadD-)") (class "Default")
      (node (ref "J2") (pin "D-") (pinfunction "D-_D-") (pintype "bidirectional"))
    )
    (net (code "76") (name "unconnected-(LIPO-PAD1-PadNC1)") (class "Default")
      (node (ref "LIPO") (pin "NC1") (pinfunction "PAD1_NC1") (pintype "bidirectional"))
    )
    (net (code "77") (name "unconnected-(LIPO-PAD2-PadNC2)") (class "Default")
      (node (ref "LIPO") (pin "NC2") (pinfunction "PAD2_NC2") (pintype "bidirectional"))
    )
    (net (code "78") (name "unconnected-(S1A-S-Pad3)") (class "Default")
      (node (ref "S1") (pin "3") (pinfunction "S_3") (pintype "passive"))
    )
    (net (code "79") (name "unconnected-(U$4-PadMR)") (class "Default")
      (node (ref "U$4") (pin "MR") (pinfunction "MR_MR") (pintype "bidirectional"))
    )
    (net (code "80") (name "unconnected-(U$5-PadMR)") (class "Default")
      (node (ref "U$5") (pin "MR") (pinfunction "MR_MR") (pintype "bidirectional"))
    )
    (net (code "81") (name "unconnected-(U$5-PadQ7S)") (class "Default")
      (node (ref "U$5") (pin "Q7S") (pinfunction "Q7S_Q7S") (pintype "bidirectional"))
    )
    (net (code "82") (name "unconnected-(U1-1PPS-PadP$13)") (class "Default")
      (node (ref "U1") (pin "P$13") (pinfunction "1PPS_P$13") (pintype "bidirectional"))
    )
    (net (code "83") (name "unconnected-(U1-EX_ANT-PadP$11)") (class "Default")
      (node (ref "U1") (pin "P$11") (pinfunction "EX_ANT_P$11") (pintype "bidirectional"))
    )
    (net (code "84") (name "unconnected-(U1-NC-PadP$6)") (class "Default")
      (node (ref "U1") (pin "P$6") (pinfunction "NC_P$6") (pintype "bidirectional"))
    )
    (net (code "85") (name "unconnected-(U1-NC-PadP$7)") (class "Default")
      (node (ref "U1") (pin "P$7") (pinfunction "NC_P$7") (pintype "bidirectional"))
    )
    (net (code "86") (name "unconnected-(U1-NC-PadP$15)") (class "Default")
      (node (ref "U1") (pin "P$15") (pinfunction "NC_P$15") (pintype "bidirectional"))
    )
    (net (code "87") (name "unconnected-(U1-NC-PadP$16)") (class "Default")
      (node (ref "U1") (pin "P$16") (pinfunction "NC_P$16") (pintype "bidirectional"))
    )
    (net (code "88") (name "unconnected-(U1-NC-PadP$17)") (class "Default")
      (node (ref "U1") (pin "P$17") (pinfunction "NC_P$17") (pintype "bidirectional"))
    )
    (net (code "89") (name "unconnected-(U1-NC-PadP$18)") (class "Default")
      (node (ref "U1") (pin "P$18") (pinfunction "NC_P$18") (pintype "bidirectional"))
    )
    (net (code "90") (name "unconnected-(U1-NC-PadP$20)") (class "Default")
      (node (ref "U1") (pin "P$20") (pinfunction "NC_P$20") (pintype "bidirectional"))
    )
    (net (code "91") (name "unconnected-(U1-NRESET-PadP$2)") (class "Default")
      (node (ref "U1") (pin "P$2") (pinfunction "NRESET_P$2") (pintype "bidirectional"))
    )
    (net (code "92") (name "unconnected-(U1-RTCM-PadP$14)") (class "Default")
      (node (ref "U1") (pin "P$14") (pinfunction "RTCM_P$14") (pintype "bidirectional"))
    )
    (net (code "93") (name "unconnected-(U1-RX-PadP$10)") (class "Default")
      (node (ref "U1") (pin "P$10") (pinfunction "RX_P$10") (pintype "bidirectional"))
    )
    (net (code "94") (name "unconnected-(U2-PTA2-Pad24)") (class "Default")
      (node (ref "U2") (pin "24") (pinfunction "PTA2_24") (pintype "bidirectional"))
    )
    (net (code "95") (name "unconnected-(U2-PTA5-Pad27)") (class "Default")
      (node (ref "U2") (pin "27") (pinfunction "PTA5_27") (pintype "bidirectional"))
    )
    (net (code "96") (name "unconnected-(U2-PTA7-Pad64)") (class "Default")
      (node (ref "U2") (pin "64") (pinfunction "PTA7_64") (pintype "bidirectional"))
    )
    (net (code "97") (name "unconnected-(U2-PTA12-Pad28)") (class "Default")
      (node (ref "U2") (pin "28") (pinfunction "PTA12_28") (pintype "bidirectional"))
    )
    (net (code "98") (name "unconnected-(U2-PTA13-Pad29)") (class "Default")
      (node (ref "U2") (pin "29") (pinfunction "PTA13_29") (pintype "bidirectional"))
    )
    (net (code "99") (name "unconnected-(U2-PTA18-Pad32)") (class "Default")
      (node (ref "U2") (pin "32") (pinfunction "PTA18_32") (pintype "bidirectional"))
    )
    (net (code "100") (name "unconnected-(U2-PTA19-Pad33)") (class "Default")
      (node (ref "U2") (pin "33") (pinfunction "PTA19_33") (pintype "bidirectional"))
    )
    (net (code "101") (name "unconnected-(U2-PTA20-Pad34)") (class "Default")
      (node (ref "U2") (pin "34") (pinfunction "PTA20_34") (pintype "bidirectional"))
    )
    (net (code "102") (name "unconnected-(U2-PTB0{slash}LLWU_P5-Pad35)") (class "Default")
      (node (ref "U2") (pin "35") (pinfunction "PTB0/LLWU_P5_35") (pintype "bidirectional"))
    )
    (net (code "103") (name "unconnected-(U2-PTB1-Pad36)") (class "Default")
      (node (ref "U2") (pin "36") (pinfunction "PTB1_36") (pintype "bidirectional"))
    )
    (net (code "104") (name "unconnected-(U2-PTB2-Pad37)") (class "Default")
      (node (ref "U2") (pin "37") (pinfunction "PTB2_37") (pintype "bidirectional"))
    )
    (net (code "105") (name "unconnected-(U2-PTB3-Pad38)") (class "Default")
      (node (ref "U2") (pin "38") (pinfunction "PTB3_38") (pintype "bidirectional"))
    )
    (net (code "106") (name "unconnected-(U2-PTB16-Pad39)") (class "Default")
      (node (ref "U2") (pin "39") (pinfunction "PTB16_39") (pintype "bidirectional"))
    )
    (net (code "107") (name "unconnected-(U2-PTB18-Pad41)") (class "Default")
      (node (ref "U2") (pin "41") (pinfunction "PTB18_41") (pintype "bidirectional"))
    )
    (net (code "108") (name "unconnected-(U2-PTC1{slash}LLWU_P6{slash}RTC_CLKIN-Pad44)") (class "Default")
      (node (ref "U2") (pin "44") (pinfunction "PTC1/LLWU_P6/RTC_CLKIN_44") (pintype "bidirectional"))
    )
    (net (code "109") (name "unconnected-(U2-PTC3{slash}LLWU_P7-Pad46)") (class "Default")
      (node (ref "U2") (pin "46") (pinfunction "PTC3/LLWU_P7_46") (pintype "bidirectional"))
    )
    (net (code "110") (name "unconnected-(U2-PTC5{slash}LLWU_P9-Pad50)") (class "Default")
      (node (ref "U2") (pin "50") (pinfunction "PTC5/LLWU_P9_50") (pintype "bidirectional"))
    )
    (net (code "111") (name "unconnected-(U2-PTC6{slash}LLWU_P10-Pad51)") (class "Default")
      (node (ref "U2") (pin "51") (pinfunction "PTC6/LLWU_P10_51") (pintype "bidirectional"))
    )
    (net (code "112") (name "unconnected-(U2-PTD0-Pad57)") (class "Default")
      (node (ref "U2") (pin "57") (pinfunction "PTD0_57") (pintype "bidirectional"))
    )
    (net (code "113") (name "unconnected-(U2-PTD4{slash}LLWU_P14-Pad61)") (class "Default")
      (node (ref "U2") (pin "61") (pinfunction "PTD4/LLWU_P14_61") (pintype "bidirectional"))
    )
    (net (code "114") (name "unconnected-(U2-PTD6{slash}LLWU_P15-Pad63)") (class "Default")
      (node (ref "U2") (pin "63") (pinfunction "PTD6/LLWU_P15_63") (pintype "bidirectional"))
    )
    (net (code "115") (name "unconnected-(U2-PTE1-Pad2)") (class "Default")
      (node (ref "U2") (pin "2") (pinfunction "PTE1_2") (pintype "bidirectional"))
    )
    (net (code "116") (name "unconnected-(U2-PTE21-Pad10)") (class "Default")
      (node (ref "U2") (pin "10") (pinfunction "PTE21_10") (pintype "bidirectional"))
    )
    (net (code "117") (name "unconnected-(U2-PTE22-Pad11)") (class "Default")
      (node (ref "U2") (pin "11") (pinfunction "PTE22_11") (pintype "bidirectional"))
    )
    (net (code "118") (name "unconnected-(U2-PTE23-Pad12)") (class "Default")
      (node (ref "U2") (pin "12") (pinfunction "PTE23_12") (pintype "bidirectional"))
    )
    (net (code "119") (name "unconnected-(U2-PTE29-Pad17)") (class "Default")
      (node (ref "U2") (pin "17") (pinfunction "PTE29_17") (pintype "bidirectional"))
    )
    (net (code "120") (name "unconnected-(U2-PTE31-Pad19)") (class "Default")
      (node (ref "U2") (pin "19") (pinfunction "PTE31_19") (pintype "bidirectional"))
    )
    (net (code "121") (name "unconnected-(U2-USB0_DM-Pad6)") (class "Default")
      (node (ref "U2") (pin "6") (pinfunction "USB0_DM_6") (pintype "passive"))
    )
    (net (code "122") (name "unconnected-(U2-USB0_DP-Pad5)") (class "Default")
      (node (ref "U2") (pin "5") (pinfunction "USB0_DP_5") (pintype "passive"))
    )
    (net (code "123") (name "unconnected-(U2-VOUT33-Pad7)") (class "Default")
      (node (ref "U2") (pin "7") (pinfunction "VOUT33_7") (pintype "output"))
    )
    (net (code "124") (name "unconnected-(U2-VREGIN-Pad8)") (class "Default")
      (node (ref "U2") (pin "8") (pinfunction "VREGIN_8") (pintype "input"))
    )
  )
)
